# turnRacingMain.net
KiCad netlist of a schematic drawn in Altium Designer
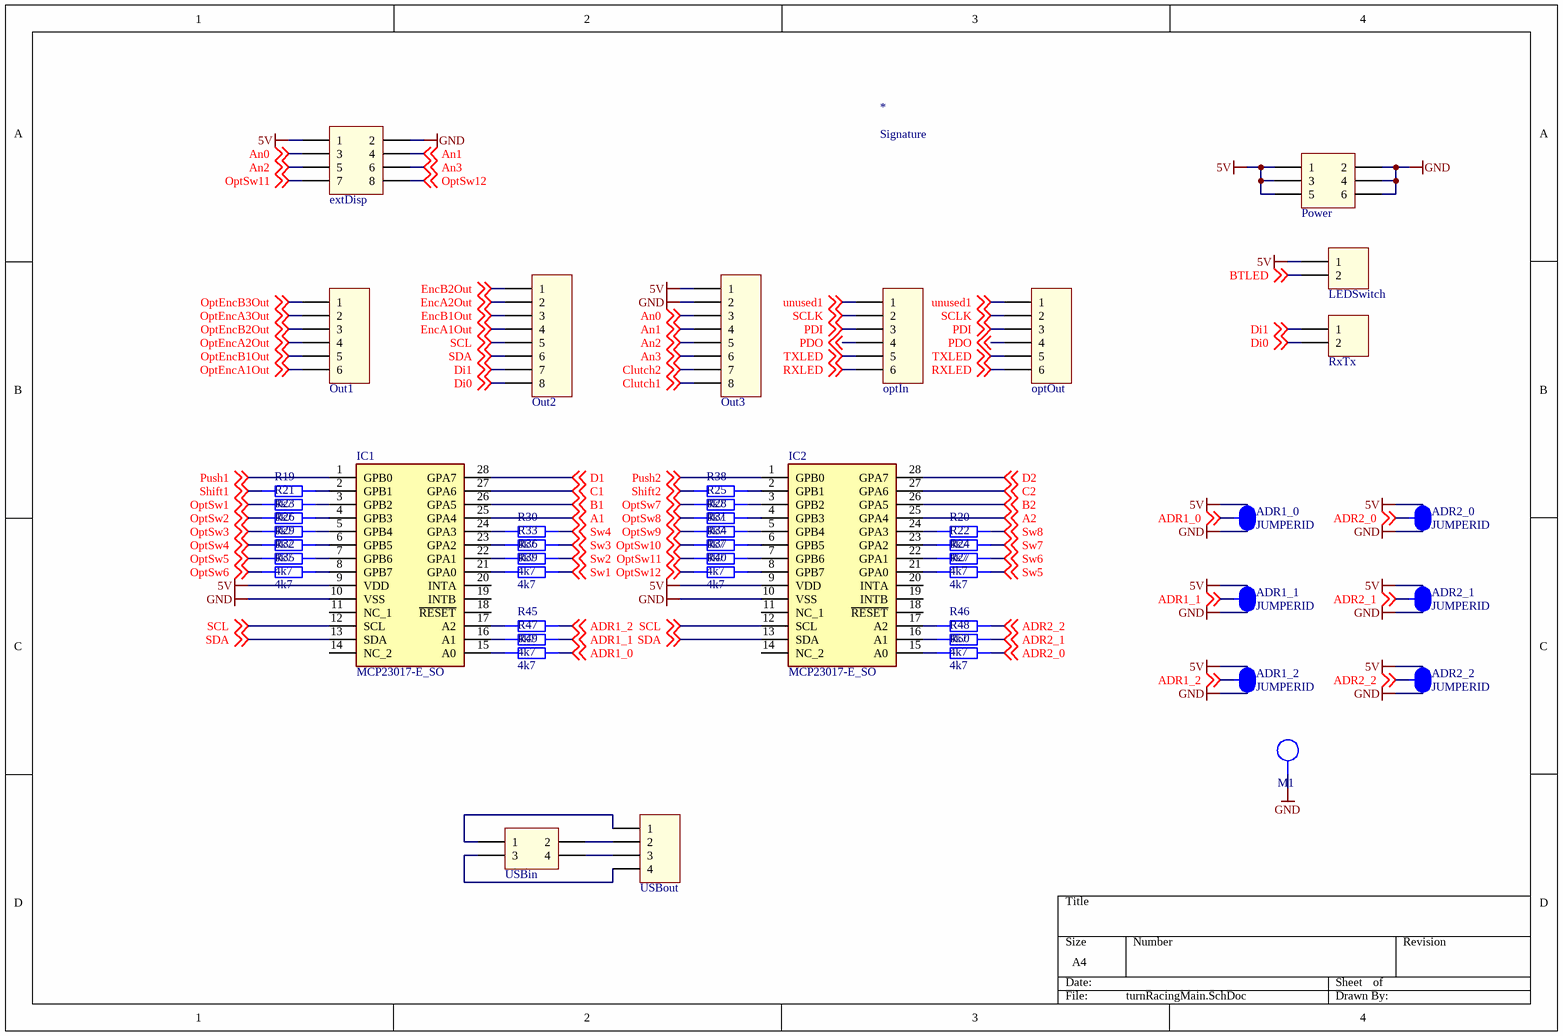
[diagram p0: turnRacingMain.SchDoc]

(export (version "E")
  (design (tool "Eeschema 10.0.6"))
  (components
    (comp (ref "*") (value "Signature") (footprint "Signature") (libsource (lib "Eric") (part "Signature")))
    (comp (ref "ADR1_0")
      (value "JUMPERID")
      (footprint "SMD-JUMPER-3")
      (libsource (lib "Standardbauteile") (part "SMD Jumper 3"))
    )
    (comp (ref "ADR1_1")
      (value "JUMPERID")
      (footprint "SMD-JUMPER-3")
      (libsource (lib "Standardbauteile") (part "SMD Jumper 3"))
    )
    (comp (ref "ADR1_2")
      (value "JUMPERID")
      (footprint "SMD-JUMPER-3")
      (libsource (lib "Standardbauteile") (part "SMD Jumper 3"))
    )
    (comp (ref "ADR2_0")
      (value "JUMPERID")
      (footprint "SMD-JUMPER-3")
      (libsource (lib "Standardbauteile") (part "SMD Jumper 3"))
    )
    (comp (ref "ADR2_1")
      (value "JUMPERID")
      (footprint "SMD-JUMPER-3")
      (libsource (lib "Standardbauteile") (part "SMD Jumper 3"))
    )
    (comp (ref "ADR2_2")
      (value "JUMPERID")
      (footprint "SMD-JUMPER-3")
      (libsource (lib "Standardbauteile") (part "SMD Jumper 3"))
    )
    (comp (ref "extDisp")
      (value "61300821121")
      (footprint "61300821121")
      (description "WR-PHD 2.54 mm THT Dual Pin Header, 8p")
      (fields (field (name "PUBLISHER") "Wurth Elektronik"))
      (libsource (lib "ALTIUM-PHD_2_54_THT_DUAL_PIN_HEADER_6130XX21121") (part "61300821121"))
    )
    (comp (ref "IC1")
      (value "MCP23017-E_SO")
      (footprint "SamacSys:SOIC127P1030X265-28N")
      (description "Integrated Circuit")
      (fields (field (name "MANUFACTURER_PART_NUMBER") "MCP23017-E/SO"))
      (libsource (lib "*") (part "MCP23017-E_SO"))
    )
    (comp (ref "IC2")
      (value "MCP23017-E_SO")
      (footprint "SamacSys:SOIC127P1030X265-28N")
      (description "Integrated Circuit")
      (fields (field (name "MANUFACTURER_PART_NUMBER") "MCP23017-E/SO"))
      (libsource (lib "*") (part "MCP23017-E_SO"))
    )
    (comp (ref "LEDSwitch")
      (value "61300211121")
      (footprint "61300211121")
      (description "WR-PHD 2.54 mm THT Pin Header, 2p")
      (fields (field (name "PUBLISHER") "Wurth Elektronik"))
      (libsource (lib "ALTIUM-PHD_2_54_THT_DUAL_PIN_HEADER_6130XX21121") (part "61300211121"))
    )
    (comp (ref "M1")
      (value "mounting pad")
      (footprint "MOUNTING_PAD_M3")
      (libsource (lib "Standardbauteile") (part "mounting pad"))
    )
    (comp (ref "optIn")
      (value "61300611121")
      (footprint "61300611121")
      (description "WR-PHD 2.54 mm THT Pin Header, 6p")
      (fields (field (name "PUBLISHER") "Wurth Elektronik"))
      (libsource (lib "ALTIUM-PHD_2_54_THT_DUAL_PIN_HEADER_6130XX21121") (part "61300611121"))
    )
    (comp (ref "optOut")
      (value "61300611121")
      (footprint "61300611121")
      (description "WR-PHD 2.54 mm THT Pin Header, 6p")
      (fields (field (name "PUBLISHER") "Wurth Elektronik"))
      (libsource (lib "ALTIUM-PHD_2_54_THT_DUAL_PIN_HEADER_6130XX21121") (part "61300611121"))
    )
    (comp (ref "Out1")
      (value "61300611121")
      (footprint "61300611121")
      (description "WR-PHD 2.54 mm THT Pin Header, 6p")
      (fields (field (name "PUBLISHER") "Wurth Elektronik"))
      (libsource (lib "ALTIUM-PHD_2_54_THT_DUAL_PIN_HEADER_6130XX21121") (part "61300611121"))
    )
    (comp (ref "Out2")
      (value "61300811121")
      (footprint "61300811121")
      (description "WR-PHD 2.54 mm THT Pin Header, 8p")
      (fields (field (name "PUBLISHER") "Wurth Elektronik"))
      (libsource (lib "ALTIUM-PHD_2_54_THT_DUAL_PIN_HEADER_6130XX21121") (part "61300811121"))
    )
    (comp (ref "Out3")
      (value "61300811121")
      (footprint "61300811121")
      (description "WR-PHD 2.54 mm THT Pin Header, 8p")
      (fields (field (name "PUBLISHER") "Wurth Elektronik"))
      (libsource (lib "ALTIUM-PHD_2_54_THT_DUAL_PIN_HEADER_6130XX21121") (part "61300811121"))
    )
    (comp (ref "Power")
      (value "61300621121")
      (footprint "61300621121")
      (description "WR-PHD 2.54 mm THT Dual Pin Header, 6p")
      (fields (field (name "PUBLISHER") "Wurth Elektronik"))
      (libsource (lib "ALTIUM-PHD_2_54_THT_DUAL_PIN_HEADER_6130XX21121") (part "61300621121"))
    )
    (comp (ref "R19")
      (value "4k7")
      (footprint "STACKPOLE CSR0603")
      (description "Resistor with multiple footprints")
      (fields (field (name "Comment") "SMD Resistor"))
      (libsource (lib "") (part "SMD Resistor_1"))
    )
    (comp (ref "R20")
      (value "4k7")
      (footprint "STACKPOLE CSR0603")
      (description "Resistor with multiple footprints")
      (fields (field (name "Comment") "SMD Resistor"))
      (libsource (lib "Standardbauteile") (part "SMD Resistor"))
    )
    (comp (ref "R21")
      (value "4k7")
      (footprint "STACKPOLE CSR0603")
      (description "Resistor with multiple footprints")
      (fields (field (name "Comment") "SMD Resistor"))
      (libsource (lib "Standardbauteile") (part "SMD Resistor"))
    )
    (comp (ref "R22")
      (value "4k7")
      (footprint "STACKPOLE CSR0603")
      (description "Resistor with multiple footprints")
      (fields (field (name "Comment") "SMD Resistor"))
      (libsource (lib "Standardbauteile") (part "SMD Resistor"))
    )
    (comp (ref "R23")
      (value "4k7")
      (footprint "STACKPOLE CSR0603")
      (description "Resistor with multiple footprints")
      (fields (field (name "Comment") "SMD Resistor"))
      (libsource (lib "Standardbauteile") (part "SMD Resistor"))
    )
    (comp (ref "R24")
      (value "4k7")
      (footprint "STACKPOLE CSR0603")
      (description "Resistor with multiple footprints")
      (fields (field (name "Comment") "SMD Resistor"))
      (libsource (lib "Standardbauteile") (part "SMD Resistor"))
    )
    (comp (ref "R25")
      (value "4k7")
      (footprint "STACKPOLE CSR0603")
      (description "Resistor with multiple footprints")
      (fields (field (name "Comment") "SMD Resistor"))
      (libsource (lib "Standardbauteile") (part "SMD Resistor"))
    )
    (comp (ref "R26")
      (value "4k7")
      (footprint "STACKPOLE CSR0603")
      (description "Resistor with multiple footprints")
      (fields (field (name "Comment") "SMD Resistor"))
      (libsource (lib "Standardbauteile") (part "SMD Resistor"))
    )
    (comp (ref "R27")
      (value "4k7")
      (footprint "STACKPOLE CSR0603")
      (description "Resistor with multiple footprints")
      (fields (field (name "Comment") "SMD Resistor"))
      (libsource (lib "Standardbauteile") (part "SMD Resistor"))
    )
    (comp (ref "R28")
      (value "4k7")
      (footprint "STACKPOLE CSR0603")
      (description "Resistor with multiple footprints")
      (fields (field (name "Comment") "SMD Resistor"))
      (libsource (lib "Standardbauteile") (part "SMD Resistor"))
    )
    (comp (ref "R29")
      (value "4k7")
      (footprint "STACKPOLE CSR0603")
      (description "Resistor with multiple footprints")
      (fields (field (name "Comment") "SMD Resistor"))
      (libsource (lib "Standardbauteile") (part "SMD Resistor"))
    )
    (comp (ref "R30")
      (value "4k7")
      (footprint "STACKPOLE CSR0603")
      (description "Resistor with multiple footprints")
      (fields (field (name "Comment") "SMD Resistor"))
      (libsource (lib "Standardbauteile") (part "SMD Resistor"))
    )
    (comp (ref "R31")
      (value "4k7")
      (footprint "STACKPOLE CSR0603")
      (description "Resistor with multiple footprints")
      (fields (field (name "Comment") "SMD Resistor"))
      (libsource (lib "Standardbauteile") (part "SMD Resistor"))
    )
    (comp (ref "R32")
      (value "4k7")
      (footprint "STACKPOLE CSR0603")
      (description "Resistor with multiple footprints")
      (fields (field (name "Comment") "SMD Resistor"))
      (libsource (lib "Standardbauteile") (part "SMD Resistor"))
    )
    (comp (ref "R33")
      (value "4k7")
      (footprint "STACKPOLE CSR0603")
      (description "Resistor with multiple footprints")
      (fields (field (name "Comment") "SMD Resistor"))
      (libsource (lib "Standardbauteile") (part "SMD Resistor"))
    )
    (comp (ref "R34")
      (value "4k7")
      (footprint "STACKPOLE CSR0603")
      (description "Resistor with multiple footprints")
      (fields (field (name "Comment") "SMD Resistor"))
      (libsource (lib "Standardbauteile") (part "SMD Resistor"))
    )
    (comp (ref "R35")
      (value "4k7")
      (footprint "STACKPOLE CSR0603")
      (description "Resistor with multiple footprints")
      (fields (field (name "Comment") "SMD Resistor"))
      (libsource (lib "Standardbauteile") (part "SMD Resistor"))
    )
    (comp (ref "R36")
      (value "4k7")
      (footprint "STACKPOLE CSR0603")
      (description "Resistor with multiple footprints")
      (fields (field (name "Comment") "SMD Resistor"))
      (libsource (lib "Standardbauteile") (part "SMD Resistor"))
    )
    (comp (ref "R37")
      (value "4k7")
      (footprint "STACKPOLE CSR0603")
      (description "Resistor with multiple footprints")
      (fields (field (name "Comment") "SMD Resistor"))
      (libsource (lib "Standardbauteile") (part "SMD Resistor"))
    )
    (comp (ref "R38")
      (value "4k7")
      (footprint "STACKPOLE CSR0603")
      (description "Resistor with multiple footprints")
      (fields (field (name "Comment") "SMD Resistor"))
      (libsource (lib "Standardbauteile") (part "SMD Resistor"))
    )
    (comp (ref "R39")
      (value "4k7")
      (footprint "STACKPOLE CSR0603")
      (description "Resistor with multiple footprints")
      (fields (field (name "Comment") "SMD Resistor"))
      (libsource (lib "Standardbauteile") (part "SMD Resistor"))
    )
    (comp (ref "R40")
      (value "4k7")
      (footprint "STACKPOLE CSR0603")
      (description "Resistor with multiple footprints")
      (fields (field (name "Comment") "SMD Resistor"))
      (libsource (lib "Standardbauteile") (part "SMD Resistor"))
    )
    (comp (ref "R45")
      (value "4k7")
      (footprint "STACKPOLE CSR0603")
      (description "Resistor with multiple footprints")
      (fields (field (name "Comment") "SMD Resistor"))
      (libsource (lib "Standardbauteile") (part "SMD Resistor"))
    )
    (comp (ref "R46")
      (value "4k7")
      (footprint "STACKPOLE CSR0603")
      (description "Resistor with multiple footprints")
      (fields (field (name "Comment") "SMD Resistor"))
      (libsource (lib "Standardbauteile") (part "SMD Resistor"))
    )
    (comp (ref "R47")
      (value "4k7")
      (footprint "STACKPOLE CSR0603")
      (description "Resistor with multiple footprints")
      (fields (field (name "Comment") "SMD Resistor"))
      (libsource (lib "Standardbauteile") (part "SMD Resistor"))
    )
    (comp (ref "R48")
      (value "4k7")
      (footprint "STACKPOLE CSR0603")
      (description "Resistor with multiple footprints")
      (fields (field (name "Comment") "SMD Resistor"))
      (libsource (lib "Standardbauteile") (part "SMD Resistor"))
    )
    (comp (ref "R49")
      (value "4k7")
      (footprint "STACKPOLE CSR0603")
      (description "Resistor with multiple footprints")
      (fields (field (name "Comment") "SMD Resistor"))
      (libsource (lib "Standardbauteile") (part "SMD Resistor"))
    )
    (comp (ref "R50")
      (value "4k7")
      (footprint "STACKPOLE CSR0603")
      (description "Resistor with multiple footprints")
      (fields (field (name "Comment") "SMD Resistor"))
      (libsource (lib "Standardbauteile") (part "SMD Resistor"))
    )
    (comp (ref "RxTx")
      (value "61300211121")
      (footprint "61300211121")
      (description "WR-PHD 2.54 mm THT Pin Header, 2p")
      (fields (field (name "PUBLISHER") "Wurth Elektronik"))
      (libsource (lib "") (part "61300211121_1"))
    )
    (comp (ref "USBin")
      (value "61300421121")
      (footprint "61300421121")
      (description "WR-PHD 2.54 mm THT Dual Pin Header, 4p")
      (fields (field (name "PUBLISHER") "Wurth Elektronik"))
      (libsource (lib "ALTIUM-PHD_2_54_THT_DUAL_PIN_HEADER_6130XX21121") (part "61300421121"))
    )
    (comp (ref "USBout")
      (value "61300411121")
      (footprint "61300411121")
      (description "WR-PHD 2.54 mm THT Pin Header, 4p")
      (fields (field (name "PUBLISHER") "Wurth Elektronik"))
      (libsource (lib "ALTIUM-PHD_2_54_THT_DUAL_PIN_HEADER_6130XX21121") (part "61300411121"))
    )
  )
  (nets
    (net (code "1") (name "5V") (class "Default")
      (node (ref "ADR1_0") (pin "3") (pinfunction "3_3") (pintype "passive"))
      (node (ref "ADR1_1") (pin "3") (pinfunction "3_3") (pintype "passive"))
      (node (ref "ADR1_2") (pin "3") (pinfunction "3_3") (pintype "passive"))
      (node (ref "ADR2_0") (pin "3") (pinfunction "3_3") (pintype "passive"))
      (node (ref "ADR2_1") (pin "3") (pinfunction "3_3") (pintype "passive"))
      (node (ref "ADR2_2") (pin "3") (pinfunction "3_3") (pintype "passive"))
      (node (ref "IC1") (pin "9") (pinfunction "VDD_9") (pintype "passive"))
      (node (ref "IC2") (pin "9") (pinfunction "VDD_9") (pintype "passive"))
      (node (ref "LEDSwitch") (pin "1") (pinfunction "1_1") (pintype "passive"))
      (node (ref "Out3") (pin "1") (pinfunction "1_1") (pintype "passive"))
      (node (ref "Power") (pin "1") (pinfunction "1_1") (pintype "passive"))
      (node (ref "Power") (pin "3") (pinfunction "3_3") (pintype "passive"))
      (node (ref "Power") (pin "5") (pinfunction "5_5") (pintype "passive"))
      (node (ref "extDisp") (pin "1") (pinfunction "1_1") (pintype "passive"))
    )
    (net (code "2") (name "A1") (class "Default")
      (node (ref "IC1") (pin "25") (pinfunction "GPA4_25") (pintype "passive"))
    )
    (net (code "3") (name "A2") (class "Default")
      (node (ref "IC2") (pin "25") (pinfunction "GPA4_25") (pintype "passive"))
    )
    (net (code "4") (name "ADR1_0") (class "Default")
      (node (ref "ADR1_0") (pin "2") (pinfunction "2_2") (pintype "passive"))
      (node (ref "R49") (pin "1") (pinfunction "1_1") (pintype "passive"))
    )
    (net (code "5") (name "ADR1_1") (class "Default")
      (node (ref "ADR1_1") (pin "2") (pinfunction "2_2") (pintype "passive"))
      (node (ref "R47") (pin "1") (pinfunction "1_1") (pintype "passive"))
    )
    (net (code "6") (name "ADR1_2") (class "Default")
      (node (ref "ADR1_2") (pin "2") (pinfunction "2_2") (pintype "passive"))
      (node (ref "R45") (pin "1") (pinfunction "1_1") (pintype "passive"))
    )
    (net (code "7") (name "ADR2_0") (class "Default")
      (node (ref "ADR2_0") (pin "2") (pinfunction "2_2") (pintype "passive"))
      (node (ref "R50") (pin "1") (pinfunction "1_1") (pintype "passive"))
    )
    (net (code "8") (name "ADR2_1") (class "Default")
      (node (ref "ADR2_1") (pin "2") (pinfunction "2_2") (pintype "passive"))
      (node (ref "R48") (pin "1") (pinfunction "1_1") (pintype "passive"))
    )
    (net (code "9") (name "ADR2_2") (class "Default")
      (node (ref "ADR2_2") (pin "2") (pinfunction "2_2") (pintype "passive"))
      (node (ref "R46") (pin "1") (pinfunction "1_1") (pintype "passive"))
    )
    (net (code "10") (name "An0") (class "Default")
      (node (ref "Out3") (pin "3") (pinfunction "3_3") (pintype "passive"))
      (node (ref "extDisp") (pin "3") (pinfunction "3_3") (pintype "passive"))
    )
    (net (code "11") (name "An1") (class "Default")
      (node (ref "Out3") (pin "4") (pinfunction "4_4") (pintype "passive"))
      (node (ref "extDisp") (pin "4") (pinfunction "4_4") (pintype "passive"))
    )
    (net (code "12") (name "An2") (class "Default")
      (node (ref "Out3") (pin "5") (pinfunction "5_5") (pintype "passive"))
      (node (ref "extDisp") (pin "5") (pinfunction "5_5") (pintype "passive"))
    )
    (net (code "13") (name "An3") (class "Default")
      (node (ref "Out3") (pin "6") (pinfunction "6_6") (pintype "passive"))
      (node (ref "extDisp") (pin "6") (pinfunction "6_6") (pintype "passive"))
    )
    (net (code "14") (name "B1") (class "Default")
      (node (ref "IC1") (pin "26") (pinfunction "GPA5_26") (pintype "passive"))
    )
    (net (code "15") (name "B2") (class "Default")
      (node (ref "IC2") (pin "26") (pinfunction "GPA5_26") (pintype "passive"))
    )
    (net (code "16") (name "BTLED") (class "Default")
      (node (ref "LEDSwitch") (pin "2") (pinfunction "2_2") (pintype "passive"))
    )
    (net (code "17") (name "C1") (class "Default")
      (node (ref "IC1") (pin "27") (pinfunction "GPA6_27") (pintype "passive"))
    )
    (net (code "18") (name "C2") (class "Default")
      (node (ref "IC2") (pin "27") (pinfunction "GPA6_27") (pintype "passive"))
    )
    (net (code "19") (name "Clutch1") (class "Default")
      (node (ref "Out3") (pin "8") (pinfunction "8_8") (pintype "passive"))
    )
    (net (code "20") (name "Clutch2") (class "Default")
      (node (ref "Out3") (pin "7") (pinfunction "7_7") (pintype "passive"))
    )
    (net (code "21") (name "D1") (class "Default")
      (node (ref "IC1") (pin "28") (pinfunction "GPA7_28") (pintype "passive"))
    )
    (net (code "22") (name "D2") (class "Default")
      (node (ref "IC2") (pin "28") (pinfunction "GPA7_28") (pintype "passive"))
    )
    (net (code "23") (name "Di0") (class "Default")
      (node (ref "Out2") (pin "8") (pinfunction "8_8") (pintype "passive"))
      (node (ref "RxTx") (pin "2") (pinfunction "2_2") (pintype "passive"))
    )
    (net (code "24") (name "Di1") (class "Default")
      (node (ref "Out2") (pin "7") (pinfunction "7_7") (pintype "passive"))
      (node (ref "RxTx") (pin "1") (pinfunction "1_1") (pintype "passive"))
    )
    (net (code "25") (name "EncA1Out") (class "Default")
      (node (ref "Out2") (pin "4") (pinfunction "4_4") (pintype "passive"))
    )
    (net (code "26") (name "EncA2Out") (class "Default")
      (node (ref "Out2") (pin "2") (pinfunction "2_2") (pintype "passive"))
    )
    (net (code "27") (name "EncB1Out") (class "Default")
      (node (ref "Out2") (pin "3") (pinfunction "3_3") (pintype "passive"))
    )
    (net (code "28") (name "EncB2Out") (class "Default")
      (node (ref "Out2") (pin "1") (pinfunction "1_1") (pintype "passive"))
    )
    (net (code "29") (name "GND") (class "Default")
      (node (ref "ADR1_0") (pin "1") (pinfunction "1_1") (pintype "passive"))
      (node (ref "ADR1_1") (pin "1") (pinfunction "1_1") (pintype "passive"))
      (node (ref "ADR1_2") (pin "1") (pinfunction "1_1") (pintype "passive"))
      (node (ref "ADR2_0") (pin "1") (pinfunction "1_1") (pintype "passive"))
      (node (ref "ADR2_1") (pin "1") (pinfunction "1_1") (pintype "passive"))
      (node (ref "ADR2_2") (pin "1") (pinfunction "1_1") (pintype "passive"))
      (node (ref "IC1") (pin "10") (pinfunction "VSS_10") (pintype "passive"))
      (node (ref "IC2") (pin "10") (pinfunction "VSS_10") (pintype "passive"))
      (node (ref "M1") (pin "1") (pintype "passive"))
      (node (ref "Out3") (pin "2") (pinfunction "2_2") (pintype "passive"))
      (node (ref "Power") (pin "2") (pinfunction "2_2") (pintype "passive"))
      (node (ref "Power") (pin "4") (pinfunction "4_4") (pintype "passive"))
      (node (ref "Power") (pin "6") (pinfunction "6_6") (pintype "passive"))
      (node (ref "extDisp") (pin "2") (pinfunction "2_2") (pintype "passive"))
    )
    (net (code "30") (name "Net-(IC1-A0)") (class "Default")
      (node (ref "IC1") (pin "15") (pinfunction "A0_15") (pintype "passive"))
      (node (ref "R49") (pin "2") (pinfunction "2_2") (pintype "passive"))
    )
    (net (code "31") (name "Net-(IC1-A1)") (class "Default")
      (node (ref "IC1") (pin "16") (pinfunction "A1_16") (pintype "passive"))
      (node (ref "R47") (pin "2") (pinfunction "2_2") (pintype "passive"))
    )
    (net (code "32") (name "Net-(IC1-A2)") (class "Default")
      (node (ref "IC1") (pin "17") (pinfunction "A2_17") (pintype "passive"))
      (node (ref "R45") (pin "2") (pinfunction "2_2") (pintype "passive"))
    )
    (net (code "33") (name "Net-(IC1-GPA0)") (class "Default")
      (node (ref "IC1") (pin "21") (pinfunction "GPA0_21") (pintype "passive"))
      (node (ref "R39") (pin "2") (pinfunction "2_2") (pintype "passive"))
    )
    (net (code "34") (name "Net-(IC1-GPA1)") (class "Default")
      (node (ref "IC1") (pin "22") (pinfunction "GPA1_22") (pintype "passive"))
      (node (ref "R36") (pin "2") (pinfunction "2_2") (pintype "passive"))
    )
    (net (code "35") (name "Net-(IC1-GPA2)") (class "Default")
      (node (ref "IC1") (pin "23") (pinfunction "GPA2_23") (pintype "passive"))
      (node (ref "R33") (pin "2") (pinfunction "2_2") (pintype "passive"))
    )
    (net (code "36") (name "Net-(IC1-GPA3)") (class "Default")
      (node (ref "IC1") (pin "24") (pinfunction "GPA3_24") (pintype "passive"))
      (node (ref "R30") (pin "2") (pinfunction "2_2") (pintype "passive"))
    )
    (net (code "37") (name "Net-(IC1-GPB1)") (class "Default")
      (node (ref "IC1") (pin "2") (pinfunction "GPB1_2") (pintype "passive"))
      (node (ref "R19") (pin "1") (pinfunction "1_1") (pintype "passive"))
    )
    (net (code "38") (name "Net-(IC1-GPB2)") (class "Default")
      (node (ref "IC1") (pin "3") (pinfunction "GPB2_3") (pintype "passive"))
      (node (ref "R21") (pin "1") (pinfunction "1_1") (pintype "passive"))
    )
    (net (code "39") (name "Net-(IC1-GPB3)") (class "Default")
      (node (ref "IC1") (pin "4") (pinfunction "GPB3_4") (pintype "passive"))
      (node (ref "R23") (pin "1") (pinfunction "1_1") (pintype "passive"))
    )
    (net (code "40") (name "Net-(IC1-GPB4)") (class "Default")
      (node (ref "IC1") (pin "5") (pinfunction "GPB4_5") (pintype "passive"))
      (node (ref "R26") (pin "1") (pinfunction "1_1") (pintype "passive"))
    )
    (net (code "41") (name "Net-(IC1-GPB5)") (class "Default")
      (node (ref "IC1") (pin "6") (pinfunction "GPB5_6") (pintype "passive"))
      (node (ref "R29") (pin "1") (pinfunction "1_1") (pintype "passive"))
    )
    (net (code "42") (name "Net-(IC1-GPB6)") (class "Default")
      (node (ref "IC1") (pin "7") (pinfunction "GPB6_7") (pintype "passive"))
      (node (ref "R32") (pin "1") (pinfunction "1_1") (pintype "passive"))
    )
    (net (code "43") (name "Net-(IC1-GPB7)") (class "Default")
      (node (ref "IC1") (pin "8") (pinfunction "GPB7_8") (pintype "passive"))
      (node (ref "R35") (pin "1") (pinfunction "1_1") (pintype "passive"))
    )
    (net (code "44") (name "Net-(IC2-A0)") (class "Default")
      (node (ref "IC2") (pin "15") (pinfunction "A0_15") (pintype "passive"))
      (node (ref "R50") (pin "2") (pinfunction "2_2") (pintype "passive"))
    )
    (net (code "45") (name "Net-(IC2-A1)") (class "Default")
      (node (ref "IC2") (pin "16") (pinfunction "A1_16") (pintype "passive"))
      (node (ref "R48") (pin "2") (pinfunction "2_2") (pintype "passive"))
    )
    (net (code "46") (name "Net-(IC2-A2)") (class "Default")
      (node (ref "IC2") (pin "17") (pinfunction "A2_17") (pintype "passive"))
      (node (ref "R46") (pin "2") (pinfunction "2_2") (pintype "passive"))
    )
    (net (code "47") (name "Net-(IC2-GPA0)") (class "Default")
      (node (ref "IC2") (pin "21") (pinfunction "GPA0_21") (pintype "passive"))
      (node (ref "R27") (pin "2") (pinfunction "2_2") (pintype "passive"))
    )
    (net (code "48") (name "Net-(IC2-GPA1)") (class "Default")
      (node (ref "IC2") (pin "22") (pinfunction "GPA1_22") (pintype "passive"))
      (node (ref "R24") (pin "2") (pinfunction "2_2") (pintype "passive"))
    )
    (net (code "49") (name "Net-(IC2-GPA2)") (class "Default")
      (node (ref "IC2") (pin "23") (pinfunction "GPA2_23") (pintype "passive"))
      (node (ref "R22") (pin "2") (pinfunction "2_2") (pintype "passive"))
    )
    (net (code "50") (name "Net-(IC2-GPA3)") (class "Default")
      (node (ref "IC2") (pin "24") (pinfunction "GPA3_24") (pintype "passive"))
      (node (ref "R20") (pin "2") (pinfunction "2_2") (pintype "passive"))
    )
    (net (code "51") (name "Net-(IC2-GPB1)") (class "Default")
      (node (ref "IC2") (pin "2") (pinfunction "GPB1_2") (pintype "passive"))
      (node (ref "R38") (pin "1") (pinfunction "1_1") (pintype "passive"))
    )
    (net (code "52") (name "Net-(IC2-GPB2)") (class "Default")
      (node (ref "IC2") (pin "3") (pinfunction "GPB2_3") (pintype "passive"))
      (node (ref "R25") (pin "1") (pinfunction "1_1") (pintype "passive"))
    )
    (net (code "53") (name "Net-(IC2-GPB3)") (class "Default")
      (node (ref "IC2") (pin "4") (pinfunction "GPB3_4") (pintype "passive"))
      (node (ref "R28") (pin "1") (pinfunction "1_1") (pintype "passive"))
    )
    (net (code "54") (name "Net-(IC2-GPB4)") (class "Default")
      (node (ref "IC2") (pin "5") (pinfunction "GPB4_5") (pintype "passive"))
      (node (ref "R31") (pin "1") (pinfunction "1_1") (pintype "passive"))
    )
    (net (code "55") (name "Net-(IC2-GPB5)") (class "Default")
      (node (ref "IC2") (pin "6") (pinfunction "GPB5_6") (pintype "passive"))
      (node (ref "R34") (pin "1") (pinfunction "1_1") (pintype "passive"))
    )
    (net (code "56") (name "Net-(IC2-GPB6)") (class "Default")
      (node (ref "IC2") (pin "7") (pinfunction "GPB6_7") (pintype "passive"))
      (node (ref "R37") (pin "1") (pinfunction "1_1") (pintype "passive"))
    )
    (net (code "57") (name "Net-(IC2-GPB7)") (class "Default")
      (node (ref "IC2") (pin "8") (pinfunction "GPB7_8") (pintype "passive"))
      (node (ref "R40") (pin "1") (pinfunction "1_1") (pintype "passive"))
    )
    (net (code "58") (name "Net-(USBin-Pad1)") (class "Default")
      (node (ref "USBin") (pin "1") (pinfunction "1_1") (pintype "passive"))
      (node (ref "USBout") (pin "1") (pinfunction "1_1") (pintype "passive"))
    )
    (net (code "59") (name "Net-(USBin-Pad2)") (class "Default")
      (node (ref "USBin") (pin "2") (pinfunction "2_2") (pintype "passive"))
      (node (ref "USBout") (pin "2") (pinfunction "2_2") (pintype "passive"))
    )
    (net (code "60") (name "Net-(USBin-Pad3)") (class "Default")
      (node (ref "USBin") (pin "3") (pinfunction "3_3") (pintype "passive"))
      (node (ref "USBout") (pin "4") (pinfunction "4_4") (pintype "passive"))
    )
    (net (code "61") (name "Net-(USBin-Pad4)") (class "Default")
      (node (ref "USBin") (pin "4") (pinfunction "4_4") (pintype "passive"))
      (node (ref "USBout") (pin "3") (pinfunction "3_3") (pintype "passive"))
    )
    (net (code "62") (name "OptEncA1Out") (class "Default")
      (node (ref "Out1") (pin "6") (pinfunction "6_6") (pintype "passive"))
    )
    (net (code "63") (name "OptEncA2Out") (class "Default")
      (node (ref "Out1") (pin "4") (pinfunction "4_4") (pintype "passive"))
    )
    (net (code "64") (name "OptEncA3Out") (class "Default")
      (node (ref "Out1") (pin "2") (pinfunction "2_2") (pintype "passive"))
    )
    (net (code "65") (name "OptEncB1Out") (class "Default")
      (node (ref "Out1") (pin "5") (pinfunction "5_5") (pintype "passive"))
    )
    (net (code "66") (name "OptEncB2Out") (class "Default")
      (node (ref "Out1") (pin "3") (pinfunction "3_3") (pintype "passive"))
    )
    (net (code "67") (name "OptEncB3Out") (class "Default")
      (node (ref "Out1") (pin "1") (pinfunction "1_1") (pintype "passive"))
    )
    (net (code "68") (name "OptSw1") (class "Default")
      (node (ref "R21") (pin "2") (pinfunction "2_2") (pintype "passive"))
    )
    (net (code "69") (name "OptSw2") (class "Default")
      (node (ref "R23") (pin "2") (pinfunction "2_2") (pintype "passive"))
    )
    (net (code "70") (name "OptSw3") (class "Default")
      (node (ref "R26") (pin "2") (pinfunction "2_2") (pintype "passive"))
    )
    (net (code "71") (name "OptSw4") (class "Default")
      (node (ref "R29") (pin "2") (pinfunction "2_2") (pintype "passive"))
    )
    (net (code "72") (name "OptSw5") (class "Default")
      (node (ref "R32") (pin "2") (pinfunction "2_2") (pintype "passive"))
    )
    (net (code "73") (name "OptSw6") (class "Default")
      (node (ref "R35") (pin "2") (pinfunction "2_2") (pintype "passive"))
    )
    (net (code "74") (name "OptSw7") (class "Default")
      (node (ref "R25") (pin "2") (pinfunction "2_2") (pintype "passive"))
    )
    (net (code "75") (name "OptSw8") (class "Default")
      (node (ref "R28") (pin "2") (pinfunction "2_2") (pintype "passive"))
    )
    (net (code "76") (name "OptSw9") (class "Default")
      (node (ref "R31") (pin "2") (pinfunction "2_2") (pintype "passive"))
    )
    (net (code "77") (name "OptSw10") (class "Default")
      (node (ref "R34") (pin "2") (pinfunction "2_2") (pintype "passive"))
    )
    (net (code "78") (name "OptSw11") (class "Default")
      (node (ref "R37") (pin "2") (pinfunction "2_2") (pintype "passive"))
      (node (ref "extDisp") (pin "7") (pinfunction "7_7") (pintype "passive"))
    )
    (net (code "79") (name "OptSw12") (class "Default")
      (node (ref "R40") (pin "2") (pinfunction "2_2") (pintype "passive"))
      (node (ref "extDisp") (pin "8") (pinfunction "8_8") (pintype "passive"))
    )
    (net (code "80") (name "PDI") (class "Default")
      (node (ref "optIn") (pin "3") (pinfunction "3_3") (pintype "passive"))
      (node (ref "optOut") (pin "3") (pinfunction "3_3") (pintype "passive"))
    )
    (net (code "81") (name "PDO") (class "Default")
      (node (ref "optIn") (pin "4") (pinfunction "4_4") (pintype "passive"))
      (node (ref "optOut") (pin "4") (pinfunction "4_4") (pintype "passive"))
    )
    (net (code "82") (name "Push1") (class "Default")
      (node (ref "IC1") (pin "1") (pinfunction "GPB0_1") (pintype "passive"))
    )
    (net (code "83") (name "Push2") (class "Default")
      (node (ref "IC2") (pin "1") (pinfunction "GPB0_1") (pintype "passive"))
    )
    (net (code "84") (name "RXLED") (class "Default")
      (node (ref "optIn") (pin "6") (pinfunction "6_6") (pintype "passive"))
      (node (ref "optOut") (pin "6") (pinfunction "6_6") (pintype "passive"))
    )
    (net (code "85") (name "SCL") (class "Default")
      (node (ref "IC1") (pin "12") (pinfunction "SCL_12") (pintype "passive"))
      (node (ref "IC2") (pin "12") (pinfunction "SCL_12") (pintype "passive"))
      (node (ref "Out2") (pin "5") (pinfunction "5_5") (pintype "passive"))
    )
    (net (code "86") (name "SCLK") (class "Default")
      (node (ref "optIn") (pin "2") (pinfunction "2_2") (pintype "passive"))
      (node (ref "optOut") (pin "2") (pinfunction "2_2") (pintype "passive"))
    )
    (net (code "87") (name "SDA") (class "Default")
      (node (ref "IC1") (pin "13") (pinfunction "SDA_13") (pintype "passive"))
      (node (ref "IC2") (pin "13") (pinfunction "SDA_13") (pintype "passive"))
      (node (ref "Out2") (pin "6") (pinfunction "6_6") (pintype "passive"))
    )
    (net (code "88") (name "Shift1") (class "Default")
      (node (ref "R19") (pin "2") (pinfunction "2_2") (pintype "passive"))
    )
    (net (code "89") (name "Shift2") (class "Default")
      (node (ref "R38") (pin "2") (pinfunction "2_2") (pintype "passive"))
    )
    (net (code "90") (name "Sw1") (class "Default")
      (node (ref "R39") (pin "1") (pinfunction "1_1") (pintype "passive"))
    )
    (net (code "91") (name "Sw2") (class "Default")
      (node (ref "R36") (pin "1") (pinfunction "1_1") (pintype "passive"))
    )
    (net (code "92") (name "Sw3") (class "Default")
      (node (ref "R33") (pin "1") (pinfunction "1_1") (pintype "passive"))
    )
    (net (code "93") (name "Sw4") (class "Default")
      (node (ref "R30") (pin "1") (pinfunction "1_1") (pintype "passive"))
    )
    (net (code "94") (name "Sw5") (class "Default")
      (node (ref "R27") (pin "1") (pinfunction "1_1") (pintype "passive"))
    )
    (net (code "95") (name "Sw6") (class "Default")
      (node (ref "R24") (pin "1") (pinfunction "1_1") (pintype "passive"))
    )
    (net (code "96") (name "Sw7") (class "Default")
      (node (ref "R22") (pin "1") (pinfunction "1_1") (pintype "passive"))
    )
    (net (code "97") (name "Sw8") (class "Default")
      (node (ref "R20") (pin "1") (pinfunction "1_1") (pintype "passive"))
    )
    (net (code "98") (name "TXLED") (class "Default")
      (node (ref "optIn") (pin "5") (pinfunction "5_5") (pintype "passive"))
      (node (ref "optOut") (pin "5") (pinfunction "5_5") (pintype "passive"))
    )
    (net (code "99") (name "unconnected-(IC1-INTA-Pad20)") (class "Default")
      (node (ref "IC1") (pin "20") (pinfunction "INTA_20") (pintype "passive"))
    )
    (net (code "100") (name "unconnected-(IC1-INTB-Pad19)") (class "Default")
      (node (ref "IC1") (pin "19") (pinfunction "INTB_19") (pintype "passive"))
    )
    (net (code "101") (name "unconnected-(IC1-NC_1-Pad11)") (class "Default")
      (node (ref "IC1") (pin "11") (pinfunction "NC_1_11") (pintype "passive"))
    )
    (net (code "102") (name "unconnected-(IC1-NC_2-Pad14)") (class "Default")
      (node (ref "IC1") (pin "14") (pinfunction "NC_2_14") (pintype "passive"))
    )
    (net (code "103") (name "unconnected-(IC1-~{RESET}-Pad18)") (class "Default")
      (node (ref "IC1") (pin "18") (pinfunction "~{RESET}_18") (pintype "passive"))
    )
    (net (code "104") (name "unconnected-(IC2-INTA-Pad20)") (class "Default")
      (node (ref "IC2") (pin "20") (pinfunction "INTA_20") (pintype "passive"))
    )
    (net (code "105") (name "unconnected-(IC2-INTB-Pad19)") (class "Default")
      (node (ref "IC2") (pin "19") (pinfunction "INTB_19") (pintype "passive"))
    )
    (net (code "106") (name "unconnected-(IC2-NC_1-Pad11)") (class "Default")
      (node (ref "IC2") (pin "11") (pinfunction "NC_1_11") (pintype "passive"))
    )
    (net (code "107") (name "unconnected-(IC2-NC_2-Pad14)") (class "Default")
      (node (ref "IC2") (pin "14") (pinfunction "NC_2_14") (pintype "passive"))
    )
    (net (code "108") (name "unconnected-(IC2-~{RESET}-Pad18)") (class "Default")
      (node (ref "IC2") (pin "18") (pinfunction "~{RESET}_18") (pintype "passive"))
    )
    (net (code "109") (name "unused1") (class "Default")
      (node (ref "optIn") (pin "1") (pinfunction "1_1") (pintype "passive"))
      (node (ref "optOut") (pin "1") (pinfunction "1_1") (pintype "passive"))
    )
  )
)
